# DM2097_IMU.net
KiCad netlist of a schematic drawn in Altium Designer
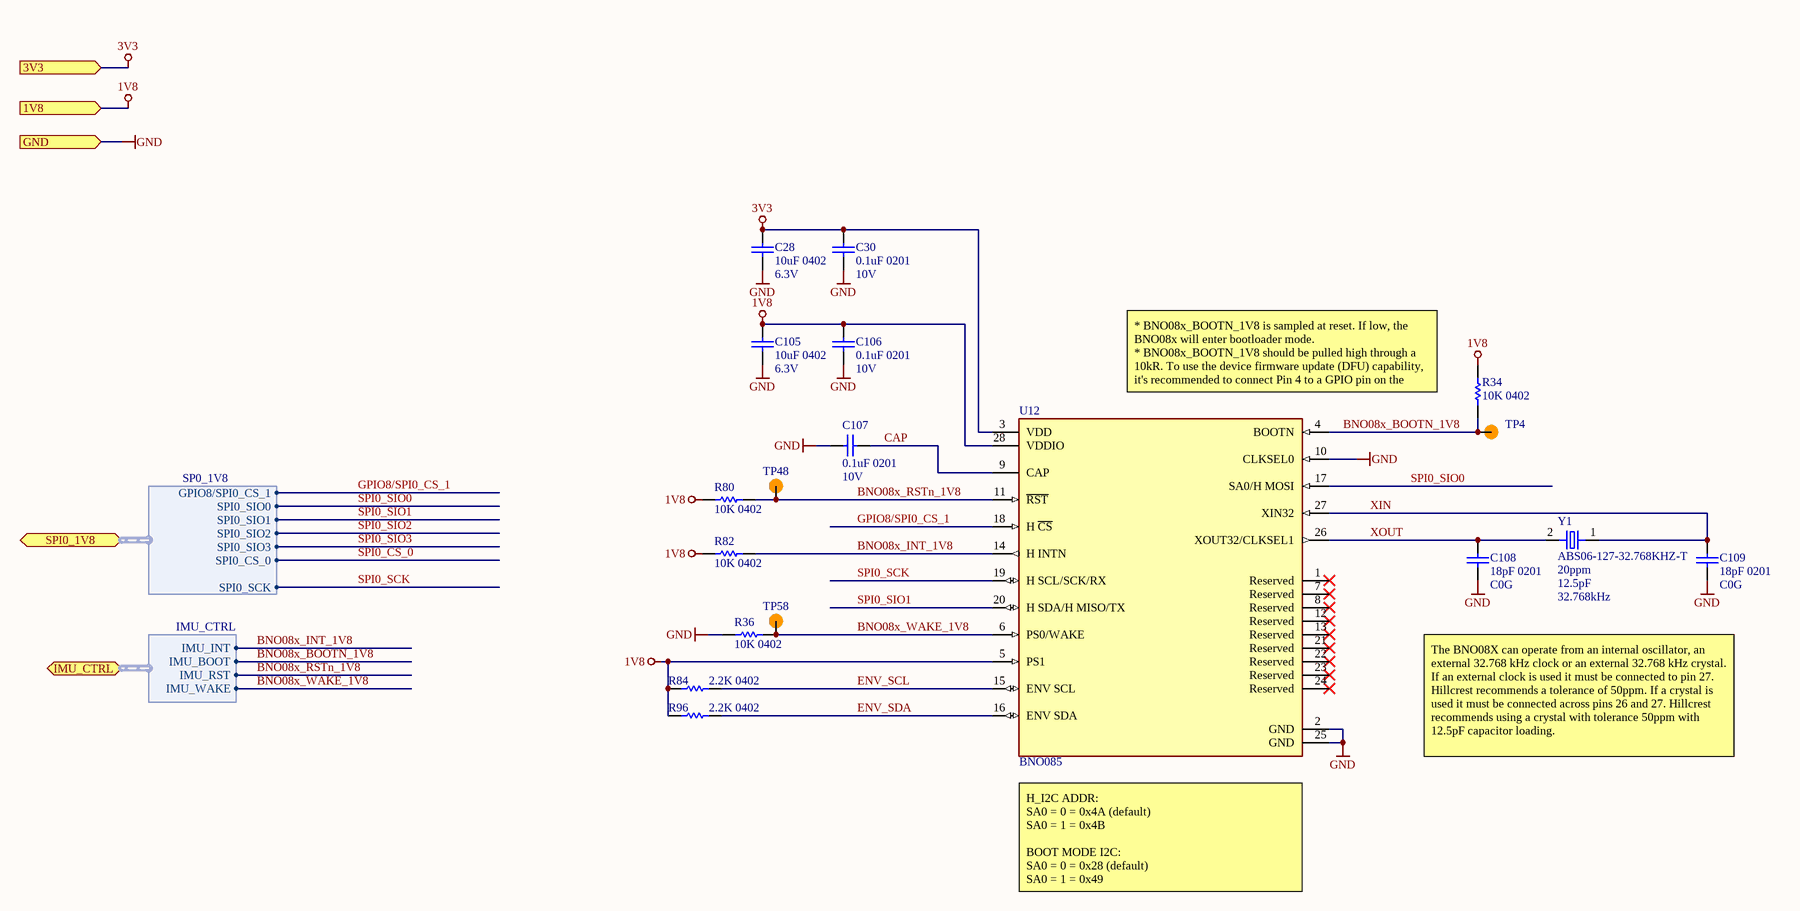
[diagram p0: DM2097_IMU.SchDoc]

(export (version "E")
  (design (tool "Eeschema 10.0.6"))
  (components
    (comp (ref "C28")
      (value "10uF 0402")
      (footprint "CAP_Altium_Vault_Generic:CAPC0402(1005)70_L")
      (description "CAP CER 10UF 6.3V X5R 0402 20%")
      (fields (field (name "TOLERANCE") "20%") (field (name "VOLTAGE RATING") "6.3V"))
      (libsource (lib "LuxonisMaster") (part "GRM155R60J106ME15D"))
    )
    (comp (ref "C30")
      (value "0.1uF 0201")
      (footprint "CAP_Altium_Vault_Generic:CAPC0201(0603)33_L")
      (description "CAP CER 0.1UF 10V X5R 0201")
      (fields (field (name "TOLERANCE") "10%") (field (name "VOLTAGE") "10V"))
      (libsource (lib "LuxonisMaster") (part "GRM033R61A104KE15D"))
    )
    (comp (ref "C105")
      (value "10uF 0402")
      (footprint "CAP_Altium_Vault_Generic:CAPC0402(1005)70_L")
      (description "CAP CER 10UF 6.3V X5R 0402 20%")
      (fields (field (name "TOLERANCE") "20%") (field (name "VOLTAGE RATING") "6.3V"))
      (libsource (lib "LuxonisMaster") (part "GRM155R60J106ME15D"))
    )
    (comp (ref "C106")
      (value "0.1uF 0201")
      (footprint "CAP_Altium_Vault_Generic:CAPC0201(0603)33_L")
      (description "CAP CER 0.1UF 10V X5R 0201")
      (fields (field (name "TOLERANCE") "10%") (field (name "VOLTAGE") "10V"))
      (libsource (lib "LuxonisMaster") (part "GRM033R61A104KE15D"))
    )
    (comp (ref "C107")
      (value "0.1uF 0201")
      (footprint "CAP_Altium_Vault_Generic:CAPC0201(0603)33_L")
      (description "CAP CER 0.1UF 10V X5R 0201")
      (fields (field (name "TOLERANCE") "10%") (field (name "VOLTAGE") "10V"))
      (libsource (lib "LuxonisMaster") (part "GRM033R61A104KE15D"))
    )
    (comp (ref "C108")
      (value "18pF 0201")
      (footprint "CAPC0201(0603)33_L")
      (description "Cap Ceramic 18pF 25V C0G 1% Pad SMD 0201 125C T/R")
      (fields (field (name "TOLERANCE") "1%") (field (name "DIELECTRIC") "C0G"))
      (libsource (lib "BW1092_R0M0E0") (part "GRM0335C1E180FA01D"))
    )
    (comp (ref "C109")
      (value "18pF 0201")
      (footprint "CAPC0201(0603)33_L")
      (description "Cap Ceramic 18pF 25V C0G 1% Pad SMD 0201 125C T/R")
      (fields (field (name "TOLERANCE") "1%") (field (name "DIELECTRIC") "C0G"))
      (libsource (lib "BW1092_R0M0E0") (part "GRM0335C1E180FA01D"))
    )
    (comp (ref "R34")
      (value "10K 0402")
      (footprint "RES_Altium_Vault_Generic:RESC0402(1005)_L")
      (fields (field (name "TOLERANCE") "1%"))
      (libsource (lib "LuxonisMaster") (part "RC0402FR-1310KL"))
    )
    (comp (ref "R36")
      (value "10K 0402")
      (footprint "RES_Altium_Vault_Generic:RESC0402(1005)_L")
      (fields (field (name "TOLERANCE") "1%"))
      (libsource (lib "LuxonisMaster") (part "RC0402FR-1310KL"))
    )
    (comp (ref "R80")
      (value "10K 0402")
      (footprint "RES_Altium_Vault_Generic:RESC0402(1005)_L")
      (fields (field (name "TOLERANCE") "1%"))
      (libsource (lib "LuxonisMaster") (part "RC0402FR-1310KL"))
    )
    (comp (ref "R82")
      (value "10K 0402")
      (footprint "RES_Altium_Vault_Generic:RESC0402(1005)_L")
      (fields (field (name "TOLERANCE") "1%"))
      (libsource (lib "LuxonisMaster") (part "RC0402FR-1310KL"))
    )
    (comp (ref "R84")
      (value "2.2K 0402")
      (footprint "RES_Altium_Vault_Generic:RESC0402(1005)_L")
      (description "RES SMD 2.2K OHM 1% 1/16W 0402")
      (fields (field (name "TOLERANCE") "1%"))
      (libsource (lib "LuxonisMaster") (part "RC0402FR-072K2L"))
    )
    (comp (ref "R96")
      (value "2.2K 0402")
      (footprint "RES_Altium_Vault_Generic:RESC0402(1005)_L")
      (description "RES SMD 2.2K OHM 1% 1/16W 0402")
      (fields (field (name "TOLERANCE") "1%"))
      (libsource (lib "LuxonisMaster") (part "RC0402FR-072K2L"))
    )
    (comp (ref "TP4")
      (value "TP100_200_NS")
      (footprint "LuxonisMaster:TP100_200_NS")
      (libsource (lib "LuxonisMaster") (part "TEST_POINT"))
    )
    (comp (ref "TP48")
      (value "TP100_200_NS")
      (footprint "LuxonisMaster:TP100_200_NS")
      (libsource (lib "LuxonisMaster") (part "TEST_POINT"))
    )
    (comp (ref "TP58")
      (value "TP100_200_NS")
      (footprint "LuxonisMaster:TP100_200_NS")
      (libsource (lib "LuxonisMaster") (part "TEST_POINT"))
    )
    (comp (ref "U12")
      (value "BNO085")
      (footprint "LuxonisMaster:BNO085")
      (description "IMU ACCEL/GYRO/MAG I2C 32BIT")
      (libsource (lib "LuxonisMaster") (part "BNO085"))
    )
    (comp (ref "Y1")
      (value "ABS06-127-32.768KHZ-T")
      (footprint "LuxonisMaster:ABS06-127-32.768KHZ-T")
      (description "CRYSTAL 32.768kHz ±20ppm Crystal 12.5pF 90 kOhms 2-SMD, No Lead")
      (fields
        (field (name "FREQUENCY TOLERANCE") "20ppm")
        (field (name "LOAD CAPACITANCE") "12.5pF")
        (field (name "FREQUENCY") "32.768kHz")
      )
      (libsource (lib "LuxonisMaster") (part "ABS06-127-32.768KHZ-T"))
    )
  )
  (nets
    (net (code "3") (name "/BNO08x_BOOTN_1V8") (class "Default")
      (node (ref "R34") (pin "1") (pinfunction "1_1") (pintype "passive"))
      (node (ref "TP4") (pin "1") (pintype "passive"))
      (node (ref "U12") (pin "4") (pinfunction "BOOTN_4") (pintype "input"))
    )
    (net (code "4") (name "/BNO08x_INT_1V8") (class "Default")
      (node (ref "R82") (pin "1") (pinfunction "1_1") (pintype "passive"))
      (node (ref "U12") (pin "14") (pinfunction "H_INTN_14") (pintype "output"))
    )
    (net (code "5") (name "/BNO08x_RSTn_1V8") (class "Default")
      (node (ref "R80") (pin "1") (pinfunction "1_1") (pintype "passive"))
      (node (ref "TP48") (pin "1") (pintype "passive"))
      (node (ref "U12") (pin "11") (pinfunction "~{RST}_11") (pintype "input"))
    )
    (net (code "6") (name "/BNO08x_WAKE_1V8") (class "Default")
      (node (ref "R36") (pin "1") (pinfunction "1_1") (pintype "passive"))
      (node (ref "TP58") (pin "1") (pintype "passive"))
      (node (ref "U12") (pin "6") (pinfunction "PS0/WAKE_6") (pintype "input"))
    )
    (net (code "7") (name "/CAP") (class "Default")
      (node (ref "C107") (pin "1") (pinfunction "1_1") (pintype "passive"))
      (node (ref "U12") (pin "9") (pinfunction "CAP_9") (pintype "passive"))
    )
    (net (code "8") (name "/ENV_SCL") (class "Default")
      (node (ref "R84") (pin "2") (pinfunction "2_2") (pintype "passive"))
      (node (ref "U12") (pin "15") (pinfunction "ENV_SCL_15") (pintype "bidirectional"))
    )
    (net (code "9") (name "/ENV_SDA") (class "Default")
      (node (ref "R96") (pin "2") (pinfunction "2_2") (pintype "passive"))
      (node (ref "U12") (pin "16") (pinfunction "ENV_SDA_16") (pintype "bidirectional"))
    )
    (net (code "10") (name "/GPIO8{slash}SPI0_CS_1") (class "Default")
      (node (ref "U12") (pin "18") (pinfunction "H_~{CS}_18") (pintype "input"))
    )
    (net (code "12") (name "/SPI0_SCK") (class "Default")
      (node (ref "U12") (pin "19") (pinfunction "H_SCL/SCK/RX_19") (pintype "bidirectional"))
    )
    (net (code "13") (name "/SPI0_SIO0") (class "Default")
      (node (ref "U12") (pin "17") (pinfunction "SA0/H_MOSI_17") (pintype "input"))
    )
    (net (code "14") (name "/SPI0_SIO1") (class "Default")
      (node (ref "U12") (pin "20") (pinfunction "H_SDA/H_MISO/TX_20") (pintype "bidirectional"))
    )
    (net (code "17") (name "/XIN") (class "Default")
      (node (ref "C109") (pin "2") (pinfunction "2_2") (pintype "passive"))
      (node (ref "U12") (pin "27") (pinfunction "XIN32_27") (pintype "input"))
      (node (ref "Y1") (pin "1") (pinfunction "1_1") (pintype "passive"))
    )
    (net (code "18") (name "/XOUT") (class "Default")
      (node (ref "C108") (pin "2") (pinfunction "2_2") (pintype "passive"))
      (node (ref "U12") (pin "26") (pinfunction "XOUT32/CLKSEL1_26") (pintype "output"))
      (node (ref "Y1") (pin "2") (pinfunction "2_2") (pintype "passive"))
    )
    (net (code "21") (name "1V8") (class "Default")
      (node (ref "C105") (pin "2") (pinfunction "2_2") (pintype "passive"))
      (node (ref "C106") (pin "2") (pinfunction "2_2") (pintype "passive"))
      (node (ref "R34") (pin "2") (pinfunction "2_2") (pintype "passive"))
      (node (ref "R80") (pin "2") (pinfunction "2_2") (pintype "passive"))
      (node (ref "R82") (pin "2") (pinfunction "2_2") (pintype "passive"))
      (node (ref "R84") (pin "1") (pinfunction "1_1") (pintype "passive"))
      (node (ref "R96") (pin "1") (pinfunction "1_1") (pintype "passive"))
      (node (ref "U12") (pin "28") (pinfunction "VDDIO_28") (pintype "power_in"))
      (node (ref "U12") (pin "5") (pinfunction "PS1_5") (pintype "input"))
    )
    (net (code "22") (name "3V3") (class "Default")
      (node (ref "C28") (pin "2") (pinfunction "2_2") (pintype "passive"))
      (node (ref "C30") (pin "2") (pinfunction "2_2") (pintype "passive"))
      (node (ref "U12") (pin "3") (pinfunction "VDD_3") (pintype "power_in"))
    )
    (net (code "23") (name "GND") (class "Default")
      (node (ref "C105") (pin "1") (pinfunction "1_1") (pintype "passive"))
      (node (ref "C106") (pin "1") (pinfunction "1_1") (pintype "passive"))
      (node (ref "C107") (pin "2") (pinfunction "2_2") (pintype "passive"))
      (node (ref "C108") (pin "1") (pinfunction "1_1") (pintype "passive"))
      (node (ref "C109") (pin "1") (pinfunction "1_1") (pintype "passive"))
      (node (ref "C28") (pin "1") (pinfunction "1_1") (pintype "passive"))
      (node (ref "C30") (pin "1") (pinfunction "1_1") (pintype "passive"))
      (node (ref "R36") (pin "2") (pinfunction "2_2") (pintype "passive"))
      (node (ref "U12") (pin "10") (pinfunction "CLKSEL0_10") (pintype "input"))
      (node (ref "U12") (pin "2") (pinfunction "GND_2") (pintype "power_in"))
      (node (ref "U12") (pin "25") (pinfunction "GND_25") (pintype "power_in"))
    )
    (net (code "24") (name "unconnected-(U12-Reserved-Pad1)") (class "Default")
      (node (ref "U12") (pin "1") (pinfunction "Reserved_1") (pintype "passive+no_connect"))
    )
    (net (code "25") (name "unconnected-(U12-Reserved-Pad7)") (class "Default")
      (node (ref "U12") (pin "7") (pinfunction "Reserved_7") (pintype "passive+no_connect"))
    )
    (net (code "26") (name "unconnected-(U12-Reserved-Pad8)") (class "Default")
      (node (ref "U12") (pin "8") (pinfunction "Reserved_8") (pintype "passive+no_connect"))
    )
    (net (code "27") (name "unconnected-(U12-Reserved-Pad12)") (class "Default")
      (node (ref "U12") (pin "12") (pinfunction "Reserved_12") (pintype "passive+no_connect"))
    )
    (net (code "28") (name "unconnected-(U12-Reserved-Pad13)") (class "Default")
      (node (ref "U12") (pin "13") (pinfunction "Reserved_13") (pintype "passive+no_connect"))
    )
    (net (code "29") (name "unconnected-(U12-Reserved-Pad21)") (class "Default")
      (node (ref "U12") (pin "21") (pinfunction "Reserved_21") (pintype "passive+no_connect"))
    )
    (net (code "30") (name "unconnected-(U12-Reserved-Pad22)") (class "Default")
      (node (ref "U12") (pin "22") (pinfunction "Reserved_22") (pintype "passive+no_connect"))
    )
    (net (code "31") (name "unconnected-(U12-Reserved-Pad23)") (class "Default")
      (node (ref "U12") (pin "23") (pinfunction "Reserved_23") (pintype "passive+no_connect"))
    )
    (net (code "32") (name "unconnected-(U12-Reserved-Pad24)") (class "Default")
      (node (ref "U12") (pin "24") (pinfunction "Reserved_24") (pintype "passive+no_connect"))
    )
  )
)
